# power.net
KiCad netlist of a schematic drawn in Altium Designer
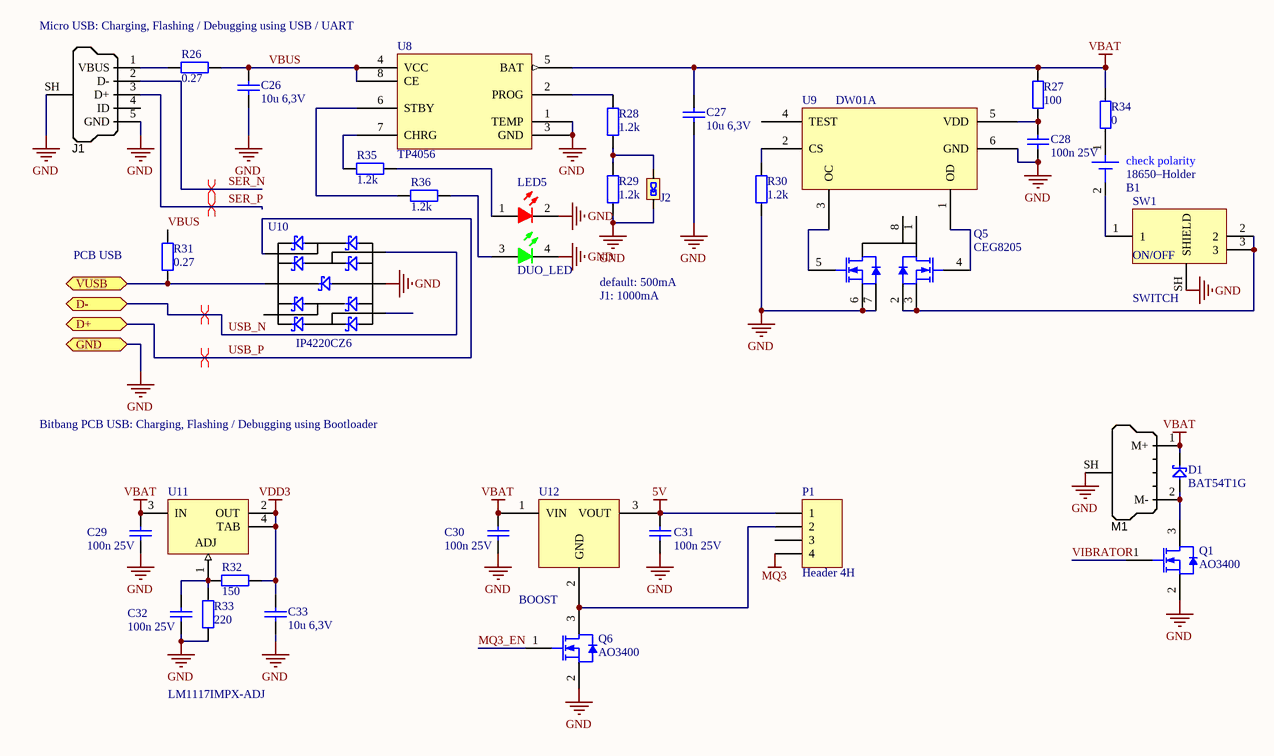
[diagram p0: power.SchDoc]

(export (version "E")
  (design (tool "Eeschema 10.0.6"))
  (components
    (comp (ref "B1")
      (value "18650–Holder")
      (footprint "18650–Holder")
      (libsource (lib "GPN–Badge") (part "18650–Holder"))
    )
    (comp (ref "C26")
      (value "10u 6,3V")
      (footprint "C-0603-H")
      (description "Capacitor 10uF 6,3V")
      (libsource (lib "Passives") (part "C-0603-10u-6,3V"))
    )
    (comp (ref "C27")
      (value "10u 6,3V")
      (footprint "C-0603-H")
      (description "Capacitor 10uF 6,3V")
      (libsource (lib "Passives") (part "C-0603-10u-6,3V"))
    )
    (comp (ref "C28")
      (value "100n 25V")
      (footprint "C-0603-M")
      (description "Capacitor 100n 25V")
      (libsource (lib "Passives") (part "C-0603-100n-25V"))
    )
    (comp (ref "C29")
      (value "100n 25V")
      (footprint "C-0603-M")
      (description "Capacitor 100n 25V")
      (libsource (lib "Passives") (part "C-0603-100n-25V"))
    )
    (comp (ref "C30")
      (value "100n 25V")
      (footprint "C-0603-M")
      (description "Capacitor 100n 25V")
      (libsource (lib "Passives") (part "C-0603-100n-25V"))
    )
    (comp (ref "C31")
      (value "100n 25V")
      (footprint "C-0603-M")
      (description "Capacitor 100n 25V")
      (libsource (lib "Passives") (part "C-0603-100n-25V"))
    )
    (comp (ref "C32")
      (value "100n 25V")
      (footprint "C-0603-M")
      (description "Capacitor 100n 25V")
      (libsource (lib "Passives") (part "C-0603-100n-25V"))
    )
    (comp (ref "C33")
      (value "10u 6,3V")
      (footprint "C-0603-H")
      (description "Capacitor 10uF 6,3V")
      (libsource (lib "Passives") (part "C-0603-10u-6,3V"))
    )
    (comp (ref "D1") (value "BAT54T1G") (footprint "SOD123") (libsource (lib "advanced") (part "D-BAT54T1G")))
    (comp (ref "J1")
      (value "USB Micro Type B (recommended if hand soldering)")
      (footprint "USB_Micro-Molex")
      (description "Connector SMD-THD USB Micro Type B middle mount")
      (libsource (lib "GPN–Badge") (part "USB_Micro_MOLEX"))
    )
    (comp (ref "J2")
      (value "jumper")
      (footprint "JUMPER 1-1")
      (libsource (lib "advanced") (part "jumper 1-1"))
    )
    (comp (ref "LED5") (value "DUO_LED") (footprint "LEDDUO") (libsource (lib "GPN–Badge") (part "DUO_LED")))
    (comp (ref "M1")
      (value "VIBRATOR")
      (footprint "VIBRATOR_SMD")
      (description "rawr")
      (libsource (lib "GPN–Badge") (part "VIBRATOR"))
    )
    (comp (ref "P1")
      (value "Header 4H")
      (footprint "HDR1X4H")
      (description "Header, 4-Pin, Right Angle")
      (fields (field (name "PUBLISHER") "Altium Limited"))
      (libsource (lib "Miscellaneous Connectors") (part "Header 4H"))
    )
    (comp (ref "Q1")
      (value "AO3400")
      (footprint "AO-SOT23-3_V")
      (description "N-channel Enhancement Mode Field-Effect Transistor; 5.8A/30V")
      (fields (field (name "MANUFACTURER") "Alpha and Omega"))
      (libsource (lib "Altium Content Vault") (part "AO-NEMOS-G1S2D3-3"))
    )
    (comp (ref "Q5")
      (value "CEG8205")
      (footprint "TSSOP8")
      (description "Dual mini mosfet 20V 4.5A")
      (libsource (lib "advanced") (part "MOSFET-CEG8205"))
    )
    (comp (ref "Q6")
      (value "AO3400")
      (footprint "AO-SOT23-3_V")
      (description "N-channel Enhancement Mode Field-Effect Transistor; 5.8A/30V")
      (fields (field (name "MANUFACTURER") "Alpha and Omega"))
      (libsource (lib "Altium Content Vault") (part "AO-NEMOS-G1S2D3-3"))
    )
    (comp (ref "R26")
      (value "0.27")
      (footprint "R-1206-M")
      (description "Resistor 0.27")
      (libsource (lib "") (part "R-1206-0R27_1"))
    )
    (comp (ref "R27")
      (value "100")
      (footprint "R-0603-M")
      (description "Resistor 100")
      (libsource (lib "Passives") (part "R-0603-100"))
    )
    (comp (ref "R28")
      (value "1.2k")
      (footprint "R-0603-M")
      (description "Resistor 1.2k")
      (libsource (lib "Passives") (part "R-0603-1k2"))
    )
    (comp (ref "R29")
      (value "1.2k")
      (footprint "R-0603-M")
      (description "Resistor 1.2k")
      (libsource (lib "Passives") (part "R-0603-1k2"))
    )
    (comp (ref "R30")
      (value "1.2k")
      (footprint "R-0603-M")
      (description "Resistor 1.2k")
      (libsource (lib "Passives") (part "R-0603-1k2"))
    )
    (comp (ref "R31")
      (value "0.27")
      (footprint "R-1206-M")
      (description "Resistor 0.27")
      (libsource (lib "Passives") (part "R-1206-0R27"))
    )
    (comp (ref "R32")
      (value "150")
      (footprint "R-0603-M")
      (description "Resistor 150")
      (libsource (lib "Passives") (part "R-0603-150"))
    )
    (comp (ref "R33")
      (value "220")
      (footprint "R-0603-M")
      (description "Resistor 220")
      (libsource (lib "Passives") (part "R-0603-220"))
    )
    (comp (ref "R34")
      (value "0")
      (footprint "R-0603-M")
      (description "Resistor 0")
      (libsource (lib "Passives") (part "R-0603-0"))
    )
    (comp (ref "R35")
      (value "1.2k")
      (footprint "R-0603-M")
      (description "Resistor 1.2k")
      (libsource (lib "") (part "R-0603-1k2_1"))
    )
    (comp (ref "R36")
      (value "1.2k")
      (footprint "R-0603-M")
      (description "Resistor 1.2k")
      (libsource (lib "") (part "R-0603-1k2_1"))
    )
    (comp (ref "SW1") (value "SWITCH") (footprint "SWITCH") (libsource (lib "GPN–Badge") (part "SWITCH")))
    (comp (ref "U8")
      (value "TP4056")
      (footprint "SOIC127P600X20_HS-9N")
      (description "1A standalone linear charging IC")
      (libsource (lib "advanced") (part "TP4056"))
    )
    (comp (ref "U9")
      (value "DW01A")
      (footprint "SOT23-6")
      (description "Single Cell LiIon LiPo Protection")
      (libsource (lib "advanced") (part "DW01A"))
    )
    (comp (ref "U10")
      (value "IP4220CZ6")
      (footprint "SOT23-6")
      (description "USB ESD Protection")
      (libsource (lib "advanced") (part "IP4220CZ6"))
    )
    (comp (ref "U11")
      (value "LM1117IMPX-ADJ")
      (footprint "MP04A_L")
      (description "800mA Low-Dropout Linear Regulator, 4-pin SOT-223")
      (fields (field (name "MANUFACTURER") "National Semiconductor"))
      (libsource (lib "Altium Content Vault") (part "PM-REG-LM1086ADJ-SOT4"))
    )
    (comp (ref "U12") (value "BOOST") (footprint "BOOST") (libsource (lib "GPN–Badge") (part "BOOST")))
  )
  (nets
    (net (code "1") (name "/MQ3_EN") (class "Default")
      (node (ref "Q6") (pin "1") (pinfunction "G_1") (pintype "passive"))
    )
    (net (code "2") (name "/SER_N") (class "Default")
      (node (ref "J1") (pin "2") (pinfunction "D-_2") (pintype "passive"))
    )
    (net (code "3") (name "/SER_P") (class "Default")
      (node (ref "J1") (pin "3") (pinfunction "D+_3") (pintype "passive"))
    )
    (net (code "4") (name "/USB_N") (class "Default")
      (node (ref "U10") (pin "3") (pinfunction "bla4_3") (pintype "passive"))
    )
    (net (code "5") (name "/USB_P") (class "Default")
      (node (ref "U10") (pin "4") (pinfunction "bla2_4") (pintype "passive"))
    )
    (net (code "6") (name "/VBUS") (class "Default")
      (node (ref "C26") (pin "2") (pinfunction "2_2") (pintype "passive"))
      (node (ref "R26") (pin "2") (pinfunction "2_2") (pintype "passive"))
      (node (ref "R31") (pin "2") (pinfunction "2_2") (pintype "passive"))
      (node (ref "U8") (pin "4") (pinfunction "VCC_4") (pintype "passive"))
      (node (ref "U8") (pin "8") (pinfunction "CE_8") (pintype "passive"))
    )
    (net (code "7") (name "/VIBRATOR") (class "Default")
      (node (ref "Q1") (pin "1") (pinfunction "G_1") (pintype "passive"))
    )
    (net (code "8") (name "/VUSB") (class "Default")
      (node (ref "R31") (pin "1") (pinfunction "1_1") (pintype "passive"))
      (node (ref "U10") (pin "5") (pinfunction "VBUS_5") (pintype "passive"))
    )
    (net (code "9") (name "5V") (class "Default")
      (node (ref "C31") (pin "2") (pinfunction "2_2") (pintype "passive"))
      (node (ref "P1") (pin "1") (pinfunction "1_1") (pintype "passive"))
      (node (ref "U12") (pin "3") (pinfunction "VOUT_3") (pintype "passive"))
    )
    (net (code "10") (name "GND") (class "Default")
      (node (ref "C26") (pin "1") (pinfunction "1_1") (pintype "passive"))
      (node (ref "C27") (pin "1") (pinfunction "1_1") (pintype "passive"))
      (node (ref "C28") (pin "1") (pinfunction "1_1") (pintype "passive"))
      (node (ref "C29") (pin "1") (pinfunction "1_1") (pintype "passive"))
      (node (ref "C30") (pin "1") (pinfunction "1_1") (pintype "passive"))
      (node (ref "C31") (pin "1") (pinfunction "1_1") (pintype "passive"))
      (node (ref "C32") (pin "1") (pinfunction "1_1") (pintype "passive"))
      (node (ref "C33") (pin "1") (pinfunction "1_1") (pintype "passive"))
      (node (ref "J1") (pin "5") (pinfunction "GND_5") (pintype "passive"))
      (node (ref "J1") (pin "SH") (pinfunction "Shell_SH") (pintype "passive"))
      (node (ref "J2") (pin "2") (pintype "passive"))
      (node (ref "LED5") (pin "2") (pinfunction "K_2") (pintype "passive"))
      (node (ref "LED5") (pin "4") (pinfunction "K_4") (pintype "passive"))
      (node (ref "M1") (pin "SH") (pinfunction "Shell_SH") (pintype "passive"))
      (node (ref "Q1") (pin "2") (pinfunction "S_2") (pintype "passive"))
      (node (ref "Q5") (pin "6") (pinfunction "S2_6") (pintype "passive"))
      (node (ref "Q5") (pin "7") (pinfunction "S2_7") (pintype "passive"))
      (node (ref "Q6") (pin "2") (pinfunction "S_2") (pintype "passive"))
      (node (ref "R29") (pin "1") (pinfunction "1_1") (pintype "passive"))
      (node (ref "R30") (pin "1") (pinfunction "1_1") (pintype "passive"))
      (node (ref "R33") (pin "1") (pinfunction "1_1") (pintype "passive"))
      (node (ref "SW1") (pin "SH") (pinfunction "SHIELD_SH") (pintype "passive"))
      (node (ref "U10") (pin "2") (pinfunction "GND_2") (pintype "passive"))
      (node (ref "U8") (pin "1") (pinfunction "TEMP_1") (pintype "passive"))
      (node (ref "U8") (pin "3") (pinfunction "GND_3") (pintype "power_in"))
      (node (ref "U9") (pin "6") (pinfunction "GND_6") (pintype "passive"))
    )
    (net (code "11") (name "MQ3") (class "Default")
      (node (ref "P1") (pin "4") (pinfunction "4_4") (pintype "passive"))
    )
    (net (code "12") (name "Net-(B1-Pad1)") (class "Default")
      (node (ref "B1") (pin "1") (pintype "passive"))
      (node (ref "R34") (pin "1") (pinfunction "1_1") (pintype "passive"))
    )
    (net (code "13") (name "Net-(B1-Pad2)") (class "Default")
      (node (ref "B1") (pin "2") (pintype "passive"))
      (node (ref "SW1") (pin "1") (pinfunction "1_1") (pintype "passive"))
    )
    (net (code "14") (name "Net-(D1-an)") (class "Default")
      (node (ref "D1") (pin "1") (pinfunction "an_1") (pintype "passive"))
      (node (ref "M1") (pin "2") (pinfunction "M-_2") (pintype "passive"))
      (node (ref "Q1") (pin "3") (pinfunction "D_3") (pintype "passive"))
    )
    (net (code "15") (name "Net-(J1-VBUS)") (class "Default")
      (node (ref "J1") (pin "1") (pinfunction "VBUS_1") (pintype "passive"))
      (node (ref "R26") (pin "1") (pinfunction "1_1") (pintype "passive"))
    )
    (net (code "16") (name "Net-(J2-Pad1)") (class "Default")
      (node (ref "J2") (pin "1") (pintype "passive"))
      (node (ref "R28") (pin "1") (pinfunction "1_1") (pintype "passive"))
      (node (ref "R29") (pin "2") (pinfunction "2_2") (pintype "passive"))
    )
    (net (code "17") (name "Net-(LED5-A-Pad1)") (class "Default")
      (node (ref "LED5") (pin "1") (pinfunction "A_1") (pintype "passive"))
      (node (ref "R35") (pin "1") (pinfunction "1_1") (pintype "passive"))
    )
    (net (code "18") (name "Net-(LED5-A-Pad3)") (class "Default")
      (node (ref "LED5") (pin "3") (pinfunction "A_3") (pintype "passive"))
      (node (ref "R36") (pin "1") (pinfunction "1_1") (pintype "passive"))
    )
    (net (code "19") (name "Net-(Q5-G1)") (class "Default")
      (node (ref "Q5") (pin "4") (pinfunction "G1_4") (pintype "passive"))
      (node (ref "U9") (pin "1") (pinfunction "OD_1") (pintype "passive"))
    )
    (net (code "20") (name "Net-(Q5-G2)") (class "Default")
      (node (ref "Q5") (pin "5") (pinfunction "G2_5") (pintype "passive"))
      (node (ref "U9") (pin "3") (pinfunction "OC_3") (pintype "passive"))
    )
    (net (code "21") (name "Net-(Q5-S1-Pad2)") (class "Default")
      (node (ref "Q5") (pin "2") (pinfunction "S1_2") (pintype "passive"))
      (node (ref "Q5") (pin "3") (pinfunction "S1_3") (pintype "passive"))
      (node (ref "SW1") (pin "2") (pinfunction "2_2") (pintype "passive"))
      (node (ref "SW1") (pin "3") (pinfunction "3_3") (pintype "passive"))
    )
    (net (code "22") (name "Net-(Q6-D)") (class "Default")
      (node (ref "P1") (pin "2") (pinfunction "2_2") (pintype "passive"))
      (node (ref "Q6") (pin "3") (pinfunction "D_3") (pintype "passive"))
      (node (ref "U12") (pin "2") (pinfunction "GND_2") (pintype "passive"))
    )
    (net (code "23") (name "Net-(U8-CHRG)") (class "Default")
      (node (ref "R35") (pin "2") (pinfunction "2_2") (pintype "passive"))
      (node (ref "U8") (pin "7") (pinfunction "CHRG_7") (pintype "passive"))
    )
    (net (code "24") (name "Net-(U8-PROG)") (class "Default")
      (node (ref "R28") (pin "2") (pinfunction "2_2") (pintype "passive"))
      (node (ref "U8") (pin "2") (pinfunction "PROG_2") (pintype "passive"))
    )
    (net (code "25") (name "Net-(U8-STBY)") (class "Default")
      (node (ref "R36") (pin "2") (pinfunction "2_2") (pintype "passive"))
      (node (ref "U8") (pin "6") (pinfunction "STBY_6") (pintype "passive"))
    )
    (net (code "26") (name "Net-(U9-CS)") (class "Default")
      (node (ref "R30") (pin "2") (pinfunction "2_2") (pintype "passive"))
      (node (ref "U9") (pin "2") (pinfunction "CS_2") (pintype "passive"))
    )
    (net (code "27") (name "Net-(U9-VDD)") (class "Default")
      (node (ref "C28") (pin "2") (pinfunction "2_2") (pintype "passive"))
      (node (ref "R27") (pin "1") (pinfunction "1_1") (pintype "passive"))
      (node (ref "U9") (pin "5") (pinfunction "VDD_5") (pintype "passive"))
    )
    (net (code "28") (name "Net-(U11-ADJ)") (class "Default")
      (node (ref "C32") (pin "2") (pinfunction "2_2") (pintype "passive"))
      (node (ref "R32") (pin "2") (pinfunction "2_2") (pintype "passive"))
      (node (ref "R33") (pin "2") (pinfunction "2_2") (pintype "passive"))
      (node (ref "U11") (pin "1") (pinfunction "ADJ_1") (pintype "input"))
    )
    (net (code "29") (name "VBAT") (class "Default")
      (node (ref "C27") (pin "2") (pinfunction "2_2") (pintype "passive"))
      (node (ref "C29") (pin "2") (pinfunction "2_2") (pintype "passive"))
      (node (ref "C30") (pin "2") (pinfunction "2_2") (pintype "passive"))
      (node (ref "D1") (pin "2") (pinfunction "kt_2") (pintype "passive"))
      (node (ref "M1") (pin "1") (pinfunction "M+_1") (pintype "passive"))
      (node (ref "R27") (pin "2") (pinfunction "2_2") (pintype "passive"))
      (node (ref "R34") (pin "2") (pinfunction "2_2") (pintype "passive"))
      (node (ref "U11") (pin "3") (pinfunction "IN_3") (pintype "power_in"))
      (node (ref "U12") (pin "1") (pinfunction "VIN_1") (pintype "passive"))
      (node (ref "U8") (pin "5") (pinfunction "BAT_5") (pintype "output"))
    )
    (net (code "30") (name "VDD3") (class "Default")
      (node (ref "C33") (pin "2") (pinfunction "2_2") (pintype "passive"))
      (node (ref "R32") (pin "1") (pinfunction "1_1") (pintype "passive"))
      (node (ref "U11") (pin "2") (pinfunction "OUT_2") (pintype "power_in"))
      (node (ref "U11") (pin "4") (pinfunction "TAB_4") (pintype "power_in"))
    )
    (net (code "31") (name "unconnected-(J1-ID-Pad4)") (class "Default")
      (node (ref "J1") (pin "4") (pinfunction "ID_4") (pintype "passive"))
    )
    (net (code "32") (name "unconnected-(P1-Pad3)") (class "Default")
      (node (ref "P1") (pin "3") (pinfunction "3_3") (pintype "passive"))
    )
    (net (code "33") (name "unconnected-(Q5-D-Pad8)") (class "Default")
      (node (ref "Q5") (pin "8") (pinfunction "D_8") (pintype "passive"))
    )
    (net (code "34") (name "unconnected-(Q5-S-Pad1)") (class "Default")
      (node (ref "Q5") (pin "1") (pinfunction "S_1") (pintype "passive"))
    )
    (net (code "35") (name "unconnected-(U9-TEST-Pad4)") (class "Default")
      (node (ref "U9") (pin "4") (pinfunction "TEST_4") (pintype "passive"))
    )
    (net (code "36") (name "unconnected-(U10-bla1-Pad6)") (class "Default")
      (node (ref "U10") (pin "6") (pinfunction "bla1_6") (pintype "passive"))
    )
    (net (code "37") (name "unconnected-(U10-bla3-Pad1)") (class "Default")
      (node (ref "U10") (pin "1") (pinfunction "bla3_1") (pintype "passive"))
    )
  )
)
